# BluCoLight.net
KiCad netlist of a schematic drawn in EAGLE
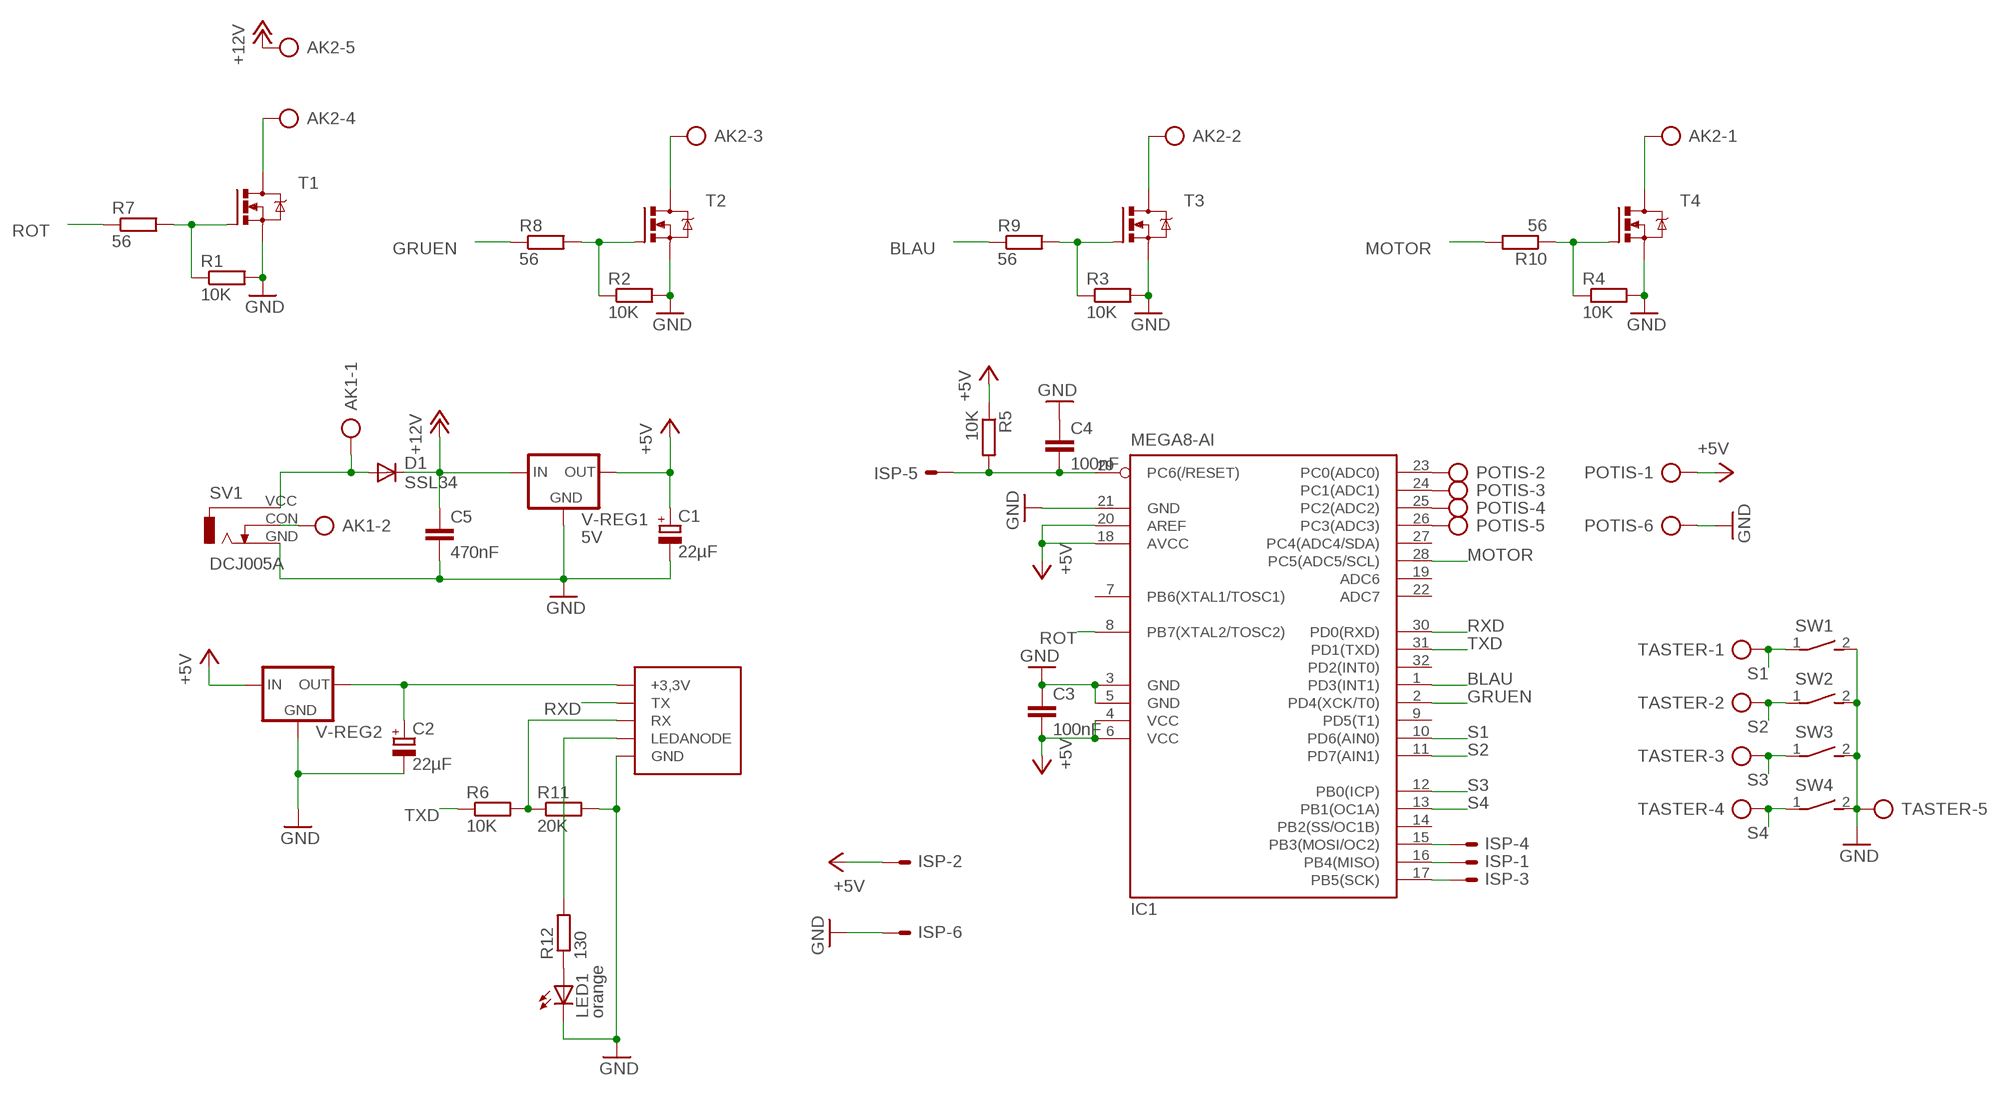
[diagram p0: schematic, sheet 1]

(export (version "E")
  (design (tool "Eeschema 10.0.6"))
  (components
    (comp (ref "AK1")
      (value "AK2")
      (footprint "eagle-import:AK_2")
      (libsource (lib "eagle-import") (part "AK2"))
    )
    (comp (ref "AK2")
      (value "AK5AK/5")
      (footprint "eagle-import:AK_5")
      (libsource (lib "eagle-import") (part "AK5AK/5"))
    )
    (comp (ref "C1")
      (value "22µF")
      (footprint "eagle-import:153CLV-0605")
      (libsource (lib "eagle-import") (part "CPOL-EU153CLV-0605"))
    )
    (comp (ref "C2")
      (value "22µF")
      (footprint "eagle-import:153CLV-0605")
      (libsource (lib "eagle-import") (part "CPOL-EU153CLV-0605"))
    )
    (comp (ref "C3")
      (value "100nF")
      (footprint "eagle-import:C0805K")
      (libsource (lib "eagle-import") (part "C-EUC0805K"))
    )
    (comp (ref "C4")
      (value "100nF")
      (footprint "eagle-import:C0805K")
      (libsource (lib "eagle-import") (part "C-EUC0805K"))
    )
    (comp (ref "C5")
      (value "470nF")
      (footprint "eagle-import:C1210K")
      (libsource (lib "eagle-import") (part "C-EUC1210K"))
    )
    (comp (ref "D1")
      (value "SSL34")
      (footprint "eagle-import:SMC")
      (libsource (lib "eagle-import") (part "DIODE-SMC"))
    )
    (comp (ref "HC-06")
      (value "HC-06")
      (footprint "eagle-import:HC-06SMD")
      (libsource (lib "eagle-import") (part "HC-06"))
    )
    (comp (ref "IC1")
      (value "MEGA8-AI")
      (footprint "eagle-import:TQFP32-08")
      (fields (field (name "MPN") "ATMEGA8-16AU"))
      (libsource (lib "eagle-import") (part "MEGA8-AI"))
    )
    (comp (ref "ISP")
      (value "ML6E")
      (footprint "eagle-import:ML6")
      (libsource (lib "eagle-import") (part "ML6E"))
    )
    (comp (ref "LED1")
      (value "orange")
      (footprint "eagle-import:CHIP-LED0603")
      (libsource (lib "eagle-import") (part "LEDCHIP-LED0603"))
    )
    (comp (ref "POTIS")
      (value "AK6PAD/6")
      (footprint "eagle-import:PAD_6")
      (libsource (lib "eagle-import") (part "AK6PAD/6"))
    )
    (comp (ref "R1")
      (value "10K")
      (footprint "eagle-import:R0603")
      (libsource (lib "eagle-import") (part "R-EUR0603"))
    )
    (comp (ref "R2")
      (value "10K")
      (footprint "eagle-import:R0603")
      (libsource (lib "eagle-import") (part "R-EUR0603"))
    )
    (comp (ref "R3")
      (value "10K")
      (footprint "eagle-import:R0603")
      (libsource (lib "eagle-import") (part "R-EUR0603"))
    )
    (comp (ref "R4")
      (value "10K")
      (footprint "eagle-import:R0603")
      (libsource (lib "eagle-import") (part "R-EUR0603"))
    )
    (comp (ref "R5")
      (value "10K")
      (footprint "eagle-import:R0603")
      (libsource (lib "eagle-import") (part "R-EUR0603"))
    )
    (comp (ref "R6")
      (value "10K")
      (footprint "eagle-import:R0603")
      (libsource (lib "eagle-import") (part "R-EUR0603"))
    )
    (comp (ref "R7")
      (value "56")
      (footprint "eagle-import:R0603")
      (libsource (lib "eagle-import") (part "R-EUR0603"))
    )
    (comp (ref "R8")
      (value "56")
      (footprint "eagle-import:R0603")
      (libsource (lib "eagle-import") (part "R-EUR0603"))
    )
    (comp (ref "R9")
      (value "56")
      (footprint "eagle-import:R0603")
      (libsource (lib "eagle-import") (part "R-EUR0603"))
    )
    (comp (ref "R10")
      (value "56")
      (footprint "eagle-import:R0603")
      (libsource (lib "eagle-import") (part "R-EUR0603"))
    )
    (comp (ref "R11")
      (value "20K")
      (footprint "eagle-import:R0603")
      (libsource (lib "eagle-import") (part "R-EUR0603"))
    )
    (comp (ref "R12")
      (value "130")
      (footprint "eagle-import:R0603")
      (libsource (lib "eagle-import") (part "R-EUR0603"))
    )
    (comp (ref "SV1")
      (value "DCJ005A")
      (footprint "eagle-import:DC005A")
      (libsource (lib "eagle-import") (part "DCJ005A"))
    )
    (comp (ref "SW1")
      (value "TASTER36SMD")
      (footprint "eagle-import:3_6_2.5SMD_TASTER")
      (libsource (lib "eagle-import") (part "TASTER36SMD"))
    )
    (comp (ref "SW2")
      (value "TASTER36SMD")
      (footprint "eagle-import:3_6_2.5SMD_TASTER")
      (libsource (lib "eagle-import") (part "TASTER36SMD"))
    )
    (comp (ref "SW3")
      (value "TASTER36SMD")
      (footprint "eagle-import:3_6_2.5SMD_TASTER")
      (libsource (lib "eagle-import") (part "TASTER36SMD"))
    )
    (comp (ref "SW4")
      (value "TASTER36SMD")
      (footprint "eagle-import:3_6_2.5SMD_TASTER")
      (libsource (lib "eagle-import") (part "TASTER36SMD"))
    )
    (comp (ref "T1")
      (value "IRLZ34NSPBFD2PACK")
      (footprint "eagle-import:D2PACK")
      (libsource (lib "eagle-import") (part "IRLZ34NSPBFD2PACK"))
    )
    (comp (ref "T2")
      (value "IRLZ34NSPBFD2PACK")
      (footprint "eagle-import:D2PACK")
      (libsource (lib "eagle-import") (part "IRLZ34NSPBFD2PACK"))
    )
    (comp (ref "T3")
      (value "IRLZ34NSPBFD2PACK")
      (footprint "eagle-import:D2PACK")
      (libsource (lib "eagle-import") (part "IRLZ34NSPBFD2PACK"))
    )
    (comp (ref "T4")
      (value "IRLZ34NSPBFD2PACK")
      (footprint "eagle-import:D2PACK")
      (libsource (lib "eagle-import") (part "IRLZ34NSPBFD2PACK"))
    )
    (comp (ref "TASTER")
      (value "AK5PAD/5")
      (footprint "eagle-import:PAD_5")
      (libsource (lib "eagle-import") (part "AK5PAD/5"))
    )
    (comp (ref "V-REG1")
      (value "5V")
      (footprint "eagle-import:SOT223")
      (libsource (lib "eagle-import") (part "53AP_L53B(LM2940CT5-SOT223)"))
    )
    (comp (ref "V-REG2")
      (value "AMS1117-3.3SOT223")
      (footprint "eagle-import:SOT223")
      (libsource (lib "eagle-import") (part "AMS1117-3.3SOT223"))
    )
  )
  (nets
    (net (code "1") (name "+5V") (class "Default")
      (node (ref "C1") (pin "+") (pinfunction "+_+") (pintype "passive"))
      (node (ref "C3") (pin "2") (pinfunction "2_2") (pintype "passive"))
      (node (ref "IC1") (pin "18") (pinfunction "AVCC_18") (pintype "power_in"))
      (node (ref "IC1") (pin "20") (pinfunction "AREF_20") (pintype "passive"))
      (node (ref "IC1") (pin "4") (pinfunction "VCC_4") (pintype "power_in"))
      (node (ref "IC1") (pin "6") (pinfunction "VCC_6") (pintype "power_in"))
      (node (ref "ISP") (pin "2") (pinfunction "S_2") (pintype "passive"))
      (node (ref "POTIS") (pin "1") (pinfunction "KL_1") (pintype "passive"))
      (node (ref "R5") (pin "1") (pinfunction "1_1") (pintype "passive"))
      (node (ref "V-REG1") (pin "3") (pinfunction "OUT_3") (pintype "passive"))
      (node (ref "V-REG2") (pin "3") (pinfunction "IN_3") (pintype "input"))
    )
    (net (code "2") (name "+12V") (class "Default")
      (node (ref "AK2") (pin "5") (pinfunction "KL_5") (pintype "passive"))
      (node (ref "C5") (pin "1") (pinfunction "1_1") (pintype "passive"))
      (node (ref "D1") (pin "C") (pinfunction "C_C") (pintype "passive"))
      (node (ref "V-REG1") (pin "1") (pinfunction "IN_1") (pintype "input"))
    )
    (net (code "3") (name "/BLAU") (class "Default")
      (node (ref "IC1") (pin "1") (pinfunction "PD3(INT1)_1") (pintype "bidirectional"))
      (node (ref "R9") (pin "1") (pinfunction "1_1") (pintype "passive"))
    )
    (net (code "4") (name "/GRUEN") (class "Default")
      (node (ref "IC1") (pin "2") (pinfunction "PD4(XCK/T0)_2") (pintype "bidirectional"))
      (node (ref "R8") (pin "1") (pinfunction "1_1") (pintype "passive"))
    )
    (net (code "5") (name "/MOTOR") (class "Default")
      (node (ref "IC1") (pin "28") (pinfunction "PC5(ADC5/SCL)_28") (pintype "bidirectional"))
      (node (ref "R10") (pin "2") (pinfunction "2_2") (pintype "passive"))
    )
    (net (code "6") (name "/ROT") (class "Default")
      (node (ref "IC1") (pin "8") (pinfunction "PB7(XTAL2/TOSC2)_8") (pintype "bidirectional"))
      (node (ref "R7") (pin "1") (pinfunction "1_1") (pintype "passive"))
    )
    (net (code "7") (name "/RXD") (class "Default")
      (node (ref "HC-06") (pin "P$1") (pinfunction "TX_P$1") (pintype "bidirectional"))
      (node (ref "IC1") (pin "30") (pinfunction "PD0(RXD)_30") (pintype "bidirectional"))
    )
    (net (code "8") (name "/S1") (class "Default")
      (node (ref "IC1") (pin "10") (pinfunction "PD6(AIN0)_10") (pintype "bidirectional"))
      (node (ref "SW1") (pin "1") (pinfunction "P_1") (pintype "passive"))
      (node (ref "TASTER") (pin "1") (pinfunction "KL_1") (pintype "passive"))
    )
    (net (code "9") (name "/S2") (class "Default")
      (node (ref "IC1") (pin "11") (pinfunction "PD7(AIN1)_11") (pintype "bidirectional"))
      (node (ref "SW2") (pin "1") (pinfunction "P_1") (pintype "passive"))
      (node (ref "TASTER") (pin "2") (pinfunction "KL_2") (pintype "passive"))
    )
    (net (code "10") (name "/S3") (class "Default")
      (node (ref "IC1") (pin "12") (pinfunction "PB0(ICP)_12") (pintype "bidirectional"))
      (node (ref "SW3") (pin "1") (pinfunction "P_1") (pintype "passive"))
      (node (ref "TASTER") (pin "3") (pinfunction "KL_3") (pintype "passive"))
    )
    (net (code "11") (name "/S4") (class "Default")
      (node (ref "IC1") (pin "13") (pinfunction "PB1(OC1A)_13") (pintype "bidirectional"))
      (node (ref "SW4") (pin "1") (pinfunction "P_1") (pintype "passive"))
      (node (ref "TASTER") (pin "4") (pinfunction "KL_4") (pintype "passive"))
    )
    (net (code "12") (name "/TXD") (class "Default")
      (node (ref "IC1") (pin "31") (pinfunction "PD1(TXD)_31") (pintype "bidirectional"))
      (node (ref "R6") (pin "1") (pinfunction "1_1") (pintype "passive"))
    )
    (net (code "13") (name "GND") (class "Default")
      (node (ref "C1") (pin "-") (pinfunction "-_-") (pintype "passive"))
      (node (ref "C2") (pin "-") (pinfunction "-_-") (pintype "passive"))
      (node (ref "C3") (pin "1") (pinfunction "1_1") (pintype "passive"))
      (node (ref "C4") (pin "1") (pinfunction "1_1") (pintype "passive"))
      (node (ref "C5") (pin "2") (pinfunction "2_2") (pintype "passive"))
      (node (ref "HC-06") (pin "P$13") (pinfunction "GND_P$13") (pintype "power_in"))
      (node (ref "HC-06") (pin "P$21") (pinfunction "GND_P$21") (pintype "power_in"))
      (node (ref "HC-06") (pin "P$22") (pinfunction "GND_P$22") (pintype "power_in"))
      (node (ref "IC1") (pin "21") (pinfunction "GND_21") (pintype "power_in"))
      (node (ref "IC1") (pin "3") (pinfunction "GND_3") (pintype "power_in"))
      (node (ref "IC1") (pin "5") (pinfunction "GND_5") (pintype "power_in"))
      (node (ref "ISP") (pin "6") (pinfunction "S_6") (pintype "passive"))
      (node (ref "LED1") (pin "C") (pinfunction "C_C") (pintype "passive"))
      (node (ref "POTIS") (pin "6") (pinfunction "KL_6") (pintype "passive"))
      (node (ref "R1") (pin "2") (pinfunction "2_2") (pintype "passive"))
      (node (ref "R11") (pin "2") (pinfunction "2_2") (pintype "passive"))
      (node (ref "R2") (pin "2") (pinfunction "2_2") (pintype "passive"))
      (node (ref "R3") (pin "2") (pinfunction "2_2") (pintype "passive"))
      (node (ref "R4") (pin "2") (pinfunction "2_2") (pintype "passive"))
      (node (ref "SV1") (pin "GND") (pinfunction "3_GND") (pintype "passive"))
      (node (ref "SW1") (pin "2") (pinfunction "S_2") (pintype "passive"))
      (node (ref "SW2") (pin "2") (pinfunction "S_2") (pintype "passive"))
      (node (ref "SW3") (pin "2") (pinfunction "S_2") (pintype "passive"))
      (node (ref "SW4") (pin "2") (pinfunction "S_2") (pintype "passive"))
      (node (ref "T1") (pin "3") (pinfunction "S_3") (pintype "passive"))
      (node (ref "T2") (pin "3") (pinfunction "S_3") (pintype "passive"))
      (node (ref "T3") (pin "3") (pinfunction "S_3") (pintype "passive"))
      (node (ref "T4") (pin "3") (pinfunction "S_3") (pintype "passive"))
      (node (ref "TASTER") (pin "5") (pinfunction "KL_5") (pintype "passive"))
      (node (ref "V-REG1") (pin "2") (pinfunction "GND_2") (pintype "input"))
      (node (ref "V-REG1") (pin "4") (pinfunction "GND_4") (pintype "input"))
      (node (ref "V-REG2") (pin "1") (pinfunction "GND_1") (pintype "input"))
    )
    (net (code "14") (name "Net-(AK1A-KL)") (class "Default")
      (node (ref "AK1") (pin "1") (pinfunction "KL_1") (pintype "passive"))
      (node (ref "D1") (pin "A") (pinfunction "A_A") (pintype "passive"))
      (node (ref "SV1") (pin "VCC") (pinfunction "1_VCC") (pintype "passive"))
    )
    (net (code "15") (name "Net-(AK1B-KL)") (class "Default")
      (node (ref "AK1") (pin "2") (pinfunction "KL_2") (pintype "passive"))
      (node (ref "SV1") (pin "CON") (pinfunction "2_CON") (pintype "passive"))
    )
    (net (code "16") (name "Net-(AK2A-KL)") (class "Default")
      (node (ref "AK2") (pin "1") (pinfunction "KL_1") (pintype "passive"))
      (node (ref "T4") (pin "2") (pinfunction "D_2") (pintype "passive"))
    )
    (net (code "17") (name "Net-(AK2B-KL)") (class "Default")
      (node (ref "AK2") (pin "2") (pinfunction "KL_2") (pintype "passive"))
      (node (ref "T3") (pin "2") (pinfunction "D_2") (pintype "passive"))
    )
    (net (code "18") (name "Net-(AK2C-KL)") (class "Default")
      (node (ref "AK2") (pin "3") (pinfunction "KL_3") (pintype "passive"))
      (node (ref "T2") (pin "2") (pinfunction "D_2") (pintype "passive"))
    )
    (net (code "19") (name "Net-(AK2D-KL)") (class "Default")
      (node (ref "AK2") (pin "4") (pinfunction "KL_4") (pintype "passive"))
      (node (ref "T1") (pin "2") (pinfunction "D_2") (pintype "passive"))
    )
    (net (code "20") (name "Net-(HC-06-+3,3V)") (class "Default")
      (node (ref "C2") (pin "+") (pinfunction "+_+") (pintype "passive"))
      (node (ref "HC-06") (pin "P$12") (pinfunction "+3,3V_P$12") (pintype "power_in"))
      (node (ref "V-REG2") (pin "2") (pinfunction "OUT_2") (pintype "passive"))
      (node (ref "V-REG2") (pin "4") (pinfunction "OUT_4") (pintype "passive"))
    )
    (net (code "21") (name "Net-(HC-06-LEDANODE)") (class "Default")
      (node (ref "HC-06") (pin "P$24") (pinfunction "LEDANODE_P$24") (pintype "bidirectional"))
      (node (ref "R12") (pin "2") (pinfunction "2_2") (pintype "passive"))
    )
    (net (code "22") (name "Net-(HC-06-RX)") (class "Default")
      (node (ref "HC-06") (pin "P$2") (pinfunction "RX_P$2") (pintype "bidirectional"))
      (node (ref "R11") (pin "1") (pinfunction "1_1") (pintype "passive"))
      (node (ref "R6") (pin "2") (pinfunction "2_2") (pintype "passive"))
    )
    (net (code "23") (name "Net-(IC1-PB3(MOSI{slash}OC2))") (class "Default")
      (node (ref "IC1") (pin "15") (pinfunction "PB3(MOSI/OC2)_15") (pintype "bidirectional"))
      (node (ref "ISP") (pin "4") (pinfunction "S_4") (pintype "passive"))
    )
    (net (code "24") (name "Net-(IC1-PB4(MISO))") (class "Default")
      (node (ref "IC1") (pin "16") (pinfunction "PB4(MISO)_16") (pintype "bidirectional"))
      (node (ref "ISP") (pin "1") (pinfunction "S_1") (pintype "passive"))
    )
    (net (code "25") (name "Net-(IC1-PB5(SCK))") (class "Default")
      (node (ref "IC1") (pin "17") (pinfunction "PB5(SCK)_17") (pintype "bidirectional"))
      (node (ref "ISP") (pin "3") (pinfunction "S_3") (pintype "passive"))
    )
    (net (code "26") (name "Net-(IC1-PC0(ADC0))") (class "Default")
      (node (ref "IC1") (pin "23") (pinfunction "PC0(ADC0)_23") (pintype "bidirectional"))
      (node (ref "POTIS") (pin "2") (pinfunction "KL_2") (pintype "passive"))
    )
    (net (code "27") (name "Net-(IC1-PC1(ADC1))") (class "Default")
      (node (ref "IC1") (pin "24") (pinfunction "PC1(ADC1)_24") (pintype "bidirectional"))
      (node (ref "POTIS") (pin "3") (pinfunction "KL_3") (pintype "passive"))
    )
    (net (code "28") (name "Net-(IC1-PC2(ADC2))") (class "Default")
      (node (ref "IC1") (pin "25") (pinfunction "PC2(ADC2)_25") (pintype "bidirectional"))
      (node (ref "POTIS") (pin "4") (pinfunction "KL_4") (pintype "passive"))
    )
    (net (code "29") (name "Net-(IC1-PC3(ADC3))") (class "Default")
      (node (ref "IC1") (pin "26") (pinfunction "PC3(ADC3)_26") (pintype "bidirectional"))
      (node (ref "POTIS") (pin "5") (pinfunction "KL_5") (pintype "passive"))
    )
    (net (code "30") (name "Net-(IC1-PC6({slash}RESET))") (class "Default")
      (node (ref "C4") (pin "2") (pinfunction "2_2") (pintype "passive"))
      (node (ref "IC1") (pin "29") (pinfunction "PC6(/RESET)_29") (pintype "bidirectional"))
      (node (ref "ISP") (pin "5") (pinfunction "S_5") (pintype "passive"))
      (node (ref "R5") (pin "2") (pinfunction "2_2") (pintype "passive"))
    )
    (net (code "31") (name "Net-(LED1-PadA)") (class "Default")
      (node (ref "LED1") (pin "A") (pinfunction "A_A") (pintype "passive"))
      (node (ref "R12") (pin "1") (pinfunction "1_1") (pintype "passive"))
    )
    (net (code "32") (name "Net-(T1-G)") (class "Default")
      (node (ref "R1") (pin "1") (pinfunction "1_1") (pintype "passive"))
      (node (ref "R7") (pin "2") (pinfunction "2_2") (pintype "passive"))
      (node (ref "T1") (pin "1") (pinfunction "G_1") (pintype "passive"))
    )
    (net (code "33") (name "Net-(T2-G)") (class "Default")
      (node (ref "R2") (pin "1") (pinfunction "1_1") (pintype "passive"))
      (node (ref "R8") (pin "2") (pinfunction "2_2") (pintype "passive"))
      (node (ref "T2") (pin "1") (pinfunction "G_1") (pintype "passive"))
    )
    (net (code "34") (name "Net-(T3-G)") (class "Default")
      (node (ref "R3") (pin "1") (pinfunction "1_1") (pintype "passive"))
      (node (ref "R9") (pin "2") (pinfunction "2_2") (pintype "passive"))
      (node (ref "T3") (pin "1") (pinfunction "G_1") (pintype "passive"))
    )
    (net (code "35") (name "Net-(T4-G)") (class "Default")
      (node (ref "R10") (pin "1") (pinfunction "1_1") (pintype "passive"))
      (node (ref "R4") (pin "1") (pinfunction "1_1") (pintype "passive"))
      (node (ref "T4") (pin "1") (pinfunction "G_1") (pintype "passive"))
    )
    (net (code "36") (name "unconnected-(IC1-ADC6-Pad19)") (class "Default")
      (node (ref "IC1") (pin "19") (pinfunction "ADC6_19") (pintype "bidirectional"))
    )
    (net (code "37") (name "unconnected-(IC1-ADC7-Pad22)") (class "Default")
      (node (ref "IC1") (pin "22") (pinfunction "ADC7_22") (pintype "bidirectional"))
    )
    (net (code "38") (name "unconnected-(IC1-PB2(SS{slash}OC1B)-Pad14)") (class "Default")
      (node (ref "IC1") (pin "14") (pinfunction "PB2(SS/OC1B)_14") (pintype "bidirectional"))
    )
    (net (code "39") (name "unconnected-(IC1-PB6(XTAL1{slash}TOSC1)-Pad7)") (class "Default")
      (node (ref "IC1") (pin "7") (pinfunction "PB6(XTAL1/TOSC1)_7") (pintype "bidirectional"))
    )
    (net (code "40") (name "unconnected-(IC1-PC4(ADC4{slash}SDA)-Pad27)") (class "Default")
      (node (ref "IC1") (pin "27") (pinfunction "PC4(ADC4/SDA)_27") (pintype "bidirectional"))
    )
    (net (code "41") (name "unconnected-(IC1-PD2(INT0)-Pad32)") (class "Default")
      (node (ref "IC1") (pin "32") (pinfunction "PD2(INT0)_32") (pintype "bidirectional"))
    )
    (net (code "42") (name "unconnected-(IC1-PD5(T1)-Pad9)") (class "Default")
      (node (ref "IC1") (pin "9") (pinfunction "PD5(T1)_9") (pintype "bidirectional"))
    )
  )
)
